# Esquem_tico.net
KiCad netlist of a schematic drawn in Altium Designer
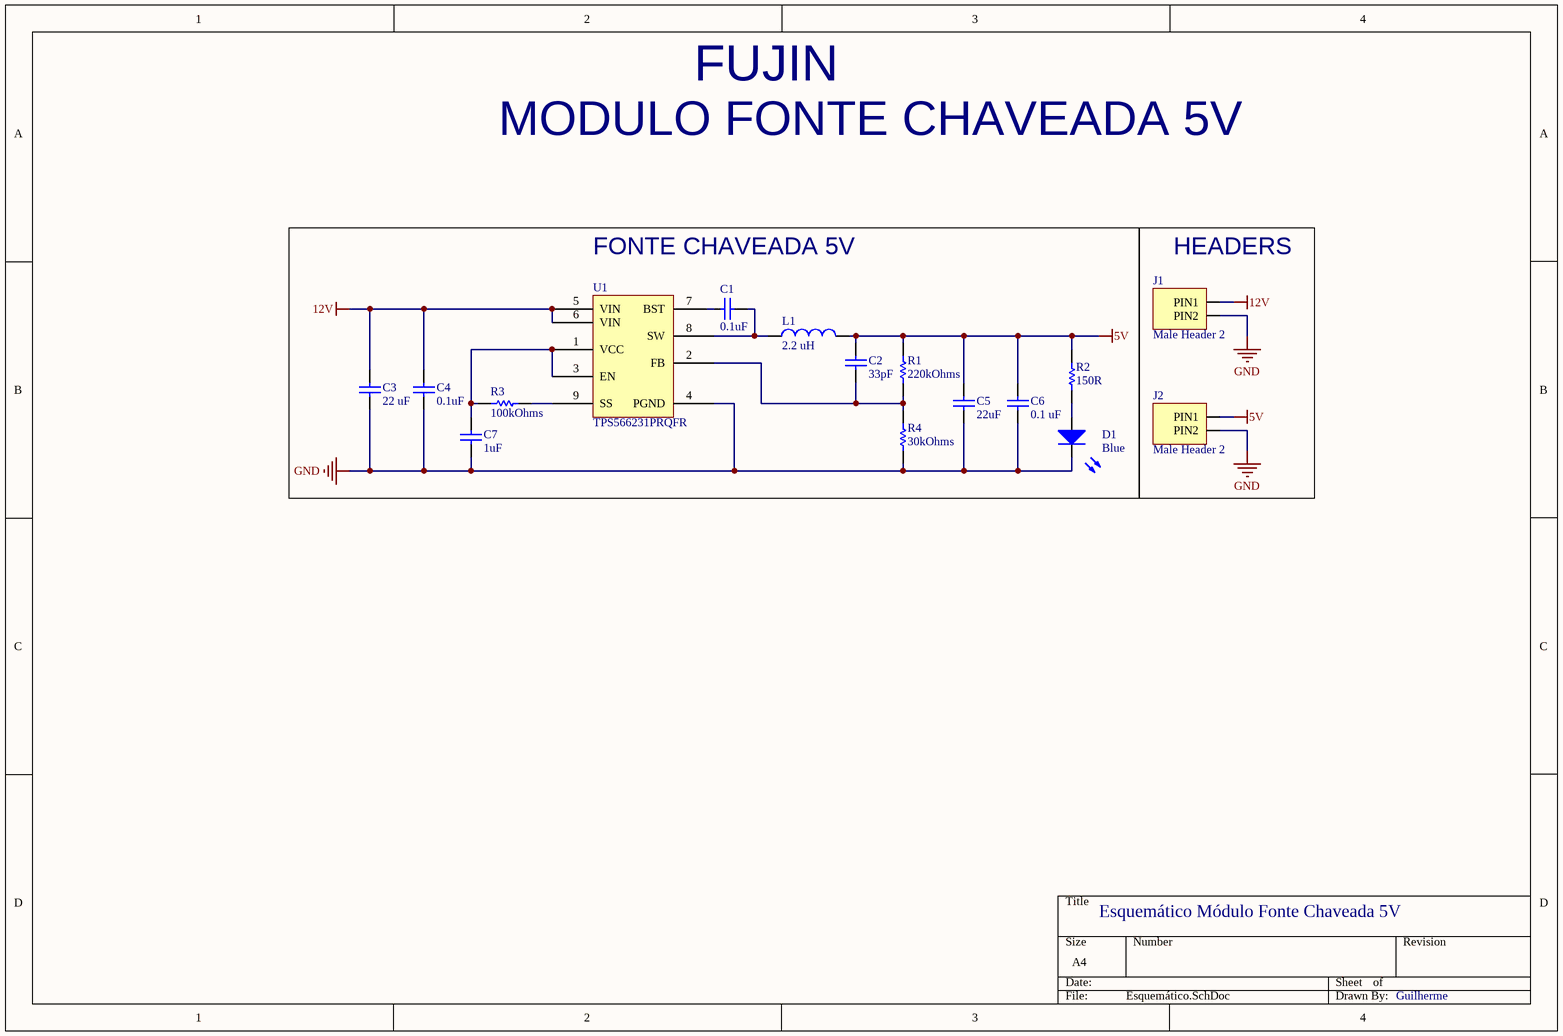
[diagram p0: Esquemático.SchDoc]

(export (version "E")
  (design (tool "Eeschema 10.0.6"))
  (components
    (comp (ref "C1")
      (value "0.1uF")
      (footprint "CAPC1005X55N")
      (description "CAP CER 0.1uF 16V X5R 0402")
      (fields
        (field (name "MANUFACTURER") "Murata")
        (field (name "PART NUMBER") "GRM155R61C104KA88D")
        (field (name "LIBRARY CONTROL - PERSON THAT CHECKED FOOTPRINT") "Guilherme")
        (field (name "LIBRARY CONTROL - PERSON THAT CHECKED SCHEMATIC") "Guilherme")
        (field (name "LIBRARY CONTROL - PERSON THAT DID THE LAST UPDATE FOOTPRINT") "Guilherme")
        (field (name "LIBRARY CONTROL - PERSON THAT DID THE LAST UPDATE SCHEMATIC") "Guilherme")
      )
      (libsource (lib "Uai!Tecas") (part "GRM155R61C104KA88D"))
    )
    (comp (ref "C2")
      (value "33pF")
      (footprint "C0201")
      (description "CAP CER 33pF 25V C0G (NP0) 0201")
      (fields
        (field (name "MANUFACTURER") "TDK")
        (field (name "PART NUMBER") "CGA1A2C0G1E330J030BA")
        (field (name "LIBRARY CONTROL - PERSON THAT CHECKED FOOTPRINT") "Guilherme")
        (field (name "LIBRARY CONTROL - PERSON THAT CHECKED SCHEMATIC") "Guilherme")
        (field (name "LIBRARY CONTROL - PERSON THAT DID THE LAST UPDATE FOOTPRINT") "Stéfany (Ster)")
        (field (name "LIBRARY CONTROL - PERSON THAT DID THE LAST UPDATE SCHEMATIC") "Guilherme")
      )
      (libsource (lib "Uai!Tecas") (part "CGA1A2C0G1E330J030BA"))
    )
    (comp (ref "C3")
      (value "22 uF")
      (footprint "C0805")
      (description "CAP CER 22UF 35V X7R 0805")
      (fields
        (field (name "MANUFACTURER") "TDK")
        (field (name "PART NUMBER") "C2012X5R1V226M125AC")
        (field (name "LIBRARY CONTROL - PERSON THAT DID THE LAST UPDATE FOOTPRINT") "Pierre")
        (field (name "LIBRARY CONTROL - PERSON THAT DID THE LAST UPDATE SCHEMATIC") "Pierre")
      )
      (libsource (lib "Uai!Tecas") (part "C2012X5R1V226M125AC"))
    )
    (comp (ref "C4")
      (value "0.1uF")
      (footprint "CAPC1608X90N")
      (description "CAP CER 0.1uF 100V X7R 0603")
      (fields
        (field (name "MANUFACTURER") "Murata")
        (field (name "PART NUMBER") "GRM188R72A104KA35D")
        (field (name "LIBRARY CONTROL - PERSON THAT CHECKED FOOTPRINT") "Guilherme")
        (field (name "LIBRARY CONTROL - PERSON THAT CHECKED SCHEMATIC") "Guilherme")
        (field (name "LIBRARY CONTROL - PERSON THAT DID THE LAST UPDATE FOOTPRINT") "Guilherme")
        (field (name "LIBRARY CONTROL - PERSON THAT DID THE LAST UPDATE SCHEMATIC") "Guilherme")
      )
      (libsource (lib "Uai!Tecas") (part "GRM188R72A104KA35D"))
    )
    (comp (ref "C5")
      (value "22uF")
      (footprint "C0805")
      (description "CAP CER 22uF 10V X5R 0805")
      (fields
        (field (name "MANUFACTURER") "Taiyo Yuden")
        (field (name "PART NUMBER") "LMK212BJ226MG-T")
        (field (name "LIBRARY CONTROL - PERSON THAT CHECKED FOOTPRINT") "Guilherme")
        (field (name "LIBRARY CONTROL - PERSON THAT CHECKED SCHEMATIC") "Guilherme")
        (field (name "LIBRARY CONTROL - PERSON THAT DID THE LAST UPDATE FOOTPRINT") "Stéfany (Ster)")
        (field (name "LIBRARY CONTROL - PERSON THAT DID THE LAST UPDATE SCHEMATIC") "Guilherme")
      )
      (libsource (lib "Uai!Tecas") (part "LMK212BJ226MG-T"))
    )
    (comp (ref "C6")
      (value "0.1 uF")
      (footprint "C0603")
      (description "CAP CER 0.1uF 25V X7R 0603")
      (fields
        (field (name "MANUFACTURER") "Murata Electronics")
        (field (name "PART NUMBER") "GRM188R71E104KA01D")
        (field (name "LIBRARY CONTROL - PERSON THAT CHECKED FOOTPRINT") "Nikaum")
        (field (name "LIBRARY CONTROL - PERSON THAT CHECKED SCHEMATIC") "Nikaum")
        (field (name "LIBRARY CONTROL - PERSON THAT DID THE LAST UPDATE FOOTPRINT") "Raquel")
        (field (name "LIBRARY CONTROL - PERSON THAT DID THE LAST UPDATE SCHEMATIC") "Nikaum")
      )
      (libsource (lib "Uai!Tecas") (part "GRM188R71E104KA01D"))
    )
    (comp (ref "C7")
      (value "1uF")
      (footprint "C1005")
      (description "CAP CER 1uF 16V X6S 0402")
      (fields
        (field (name "MANUFACTURER") "TDK")
        (field (name "PART NUMBER") "C1005X6S1C105K050BC")
        (field (name "LIBRARY CONTROL - PERSON THAT CHECKED FOOTPRINT") "Guilherme")
        (field (name "LIBRARY CONTROL - PERSON THAT CHECKED SCHEMATIC") "Guilherme")
        (field (name "LIBRARY CONTROL - PERSON THAT DID THE LAST UPDATE FOOTPRINT") "Guilherme")
        (field (name "LIBRARY CONTROL - PERSON THAT DID THE LAST UPDATE SCHEMATIC") "Guilherme")
      )
      (libsource (lib "Uai!Tecas") (part "C1005X6S1C105K050BC"))
    )
    (comp (ref "D1")
      (value "Blue")
      (footprint "DIODO_2-SMD-3215")
      (description "LED 75mW BLUE 45MCD 3215")
      (fields
        (field (name "MANUFACTURER") "Everlight Electronics")
        (field (name "PART NUMBER") "EAST3215BA5")
        (field (name "LIBRARY CONTROL - PERSON THAT CHECKED FOOTPRINT") "Lucas")
        (field (name "LIBRARY CONTROL - PERSON THAT CHECKED SCHEMATIC") "Lucas")
        (field (name "LIBRARY CONTROL - PERSON THAT DID THE LAST UPDATE FOOTPRINT") "Stéfany (Ster)")
        (field (name "LIBRARY CONTROL - PERSON THAT DID THE LAST UPDATE SCHEMATIC") "Stéfany (Ster)")
      )
      (libsource (lib "Uai!Tecas") (part "EAST3215BA5"))
    )
    (comp (ref "J1")
      (value "Male Header 2")
      (footprint "MALE HEADER 2")
      (fields
        (field (name "LIBRARY CONTROL - PERSON THAT DID THE LAST UPDATE SCHEMATIC") "Marcos")
        (field (name "LIBRARY CONTROL - PERSONT THAT DID THE LAST UPDATE FOOTPRINT") "Marcos")
      )
      (libsource (lib "Uai!Tecas") (part "Male Header 2"))
    )
    (comp (ref "J2")
      (value "Male Header 2")
      (footprint "MALE HEADER 2")
      (fields
        (field (name "LIBRARY CONTROL - PERSON THAT DID THE LAST UPDATE SCHEMATIC") "Marcos")
        (field (name "LIBRARY CONTROL - PERSONT THAT DID THE LAST UPDATE FOOTPRINT") "Marcos")
      )
      (libsource (lib "Uai!Tecas") (part "Male Header 2"))
    )
    (comp (ref "L1")
      (value "2.2 uH")
      (footprint "6045")
      (description "IND FIXED 2.2uH 7.5A 0.019OHM")
      (fields
        (field (name "MANUFACTURER") "TDK")
        (field (name "PART NUMBER") "VLS6045EX-2R2N")
        (field (name "LIBRARY CONTROL - PERSON THAT DID THE LAST UPDATE FOOTPRINT") "Marcos")
        (field (name "LIBRARY CONTROL - PERSON THAT DID THE LAST UPDATE SCHEMATIC") "Marcos")
      )
      (libsource (lib "Uai!Tecas") (part "VLS6045EX-2R2N"))
    )
    (comp (ref "R1")
      (value "220kOhms")
      (footprint "RESISTOR_0603")
      (description "RES SMD 220 kOHMS 0,1% 1/10W 0603")
      (fields
        (field (name "MANUFACTURER") "Susumu")
        (field (name "PART NUMBER") "RG1608P-224-B-T5")
        (field (name "LIBRARY CONTROL - PERSON THAT CHECKED FOOTPRINT") "Guilherme")
        (field (name "LIBRARY CONTROL - PERSON THAT CHECKED SCHEMATIC") "Guilherme")
        (field (name "LIBRARY CONTROL - PERSON THAT DID THE LAST UPDATE FOOTPRINT") "Stéfany (Ster)")
        (field (name "LIBRARY CONTROL - PERSON THAT DID THE LAST UPDATE SCHEMATIC") "Guilherme")
      )
      (libsource (lib "Uai!Tecas") (part "RG1608P-224-B-T5"))
    )
    (comp (ref "R2")
      (value "150R")
      (footprint "RESISTOR_0402")
      (description "RES SMD 150 OHM 1% 1/32W 0402")
      (fields
        (field (name "MANUFACTURER") "Vishay")
        (field (name "PART NUMBER") "CRCW0100150RFREL")
        (field (name "LIBRARY CONTROL - PERSON THAT CHECKED FOOTPRINT") "Guilherme")
        (field (name "LIBRARY CONTROL - PERSON THAT CHECKED SCHEMATIC") "Guilherme")
        (field (name "LIBRARY CONTROL - PERSON THAT DID THE LAST UPDATE FOOTPRINT") "Guilherme")
        (field (name "LIBRARY CONTROL - PERSON THAT DID THE LAST UPDATE SCHEMATIC") "Guilherme")
      )
      (libsource (lib "Uai!Tecas") (part "CRCW0100150RFREL"))
    )
    (comp (ref "R3")
      (value "100kOhms")
      (footprint "RESC1005X40N")
      (description "RES SMD 100 kOHMS 1% 1/16W 0402")
      (fields
        (field (name "MANUFACTURER") "Vishay")
        (field (name "PART NUMBER") "CRCW0402100KFKED")
        (field (name "LIBRARY CONTROL - PERSON THAT CHECKED FOOTPRINT") "Guilherme")
        (field (name "LIBRARY CONTROL - PERSON THAT CHECKED SCHEMATIC") "Guilherme")
        (field (name "LIBRARY CONTROL - PERSON THAT DID THE LAST UPDATE FOOTPRINT") "Guilherme")
        (field (name "LIBRARY CONTROL - PERSON THAT DID THE LAST UPDATE SCHEMATIC") "Guilherme")
      )
      (libsource (lib "Uai!Tecas") (part "CRCW0402100KFKED"))
    )
    (comp (ref "R4")
      (value "30kOhms")
      (footprint "RESC1608X55N")
      (description "RES SMD 30 kOHMS 1% 1/10W 0603")
      (fields
        (field (name "MANUFACTURER") "YAGEO")
        (field (name "PART NUMBER") "RC0603FR-0730KL")
        (field (name "LIBRARY CONTROL - PERSON THAT CHECKED FOOTPRINT") "Guilherme")
        (field (name "LIBRARY CONTROL - PERSON THAT CHECKED SCHEMATIC") "Guilherme")
        (field (name "LIBRARY CONTROL - PERSON THAT DID THE LAST UPDATE FOOTPRINT") "Guilherme")
        (field (name "LIBRARY CONTROL - PERSON THAT DID THE LAST UPDATE SCHEMATIC") "Guilherme")
      )
      (libsource (lib "Uai!Tecas") (part "RC0603FR-0730KL"))
    )
    (comp (ref "U1")
      (value "TPS566231PRQFR")
      (footprint "RQF0009A")
      (description "IC REG SWITCHING 4A 0,6V TO 7V")
      (fields
        (field (name "MANUFACTURER") "Texas Instruments")
        (field (name "LIBRARY CONTROL - PERSON THAT CHECKED FOOTPRINT") "Guilherme")
        (field (name "LIBRARY CONTROL - PERSON THAT CHECKED SCHEMATIC") "Guilherme")
        (field (name "LIBRARY CONTROL - PERSON THAT DID THE LAST UPDATE FOOTPRINT") "Marques")
        (field (name "LIBRARY CONTROL - PERSON THAT DID THE LAST UPDATE SCHEMATIC") "Marques")
      )
      (libsource (lib "Uai!Tecas") (part "TPS566231PRQFR"))
    )
  )
  (nets
    (net (code "1") (name "5V") (class "Default")
      (node (ref "C2") (pin "2") (pinfunction "2_2") (pintype "passive"))
      (node (ref "C5") (pin "2") (pinfunction "2_2") (pintype "passive"))
      (node (ref "C6") (pin "2") (pinfunction "2_2") (pintype "passive"))
      (node (ref "J2") (pin "PIN1") (pinfunction "PIN1_PIN1") (pintype "passive"))
      (node (ref "L1") (pin "2") (pinfunction "2_2") (pintype "passive"))
      (node (ref "R1") (pin "2") (pinfunction "2_2") (pintype "passive"))
      (node (ref "R2") (pin "2") (pinfunction "2_2") (pintype "passive"))
    )
    (net (code "2") (name "12V") (class "Default")
      (node (ref "C3") (pin "2") (pinfunction "2_2") (pintype "passive"))
      (node (ref "C4") (pin "2") (pinfunction "2_2") (pintype "passive"))
      (node (ref "J1") (pin "PIN1") (pinfunction "PIN1_PIN1") (pintype "passive"))
      (node (ref "U1") (pin "5") (pinfunction "VIN_5") (pintype "passive"))
      (node (ref "U1") (pin "6") (pinfunction "VIN_6") (pintype "passive"))
    )
    (net (code "3") (name "GND") (class "Default")
      (node (ref "C3") (pin "1") (pinfunction "1_1") (pintype "passive"))
      (node (ref "C4") (pin "1") (pinfunction "1_1") (pintype "passive"))
      (node (ref "C5") (pin "1") (pinfunction "1_1") (pintype "passive"))
      (node (ref "C6") (pin "1") (pinfunction "1_1") (pintype "passive"))
      (node (ref "C7") (pin "1") (pinfunction "1_1") (pintype "passive"))
      (node (ref "D1") (pin "C") (pinfunction "C_C") (pintype "passive"))
      (node (ref "J1") (pin "PIN2") (pinfunction "PIN2_PIN2") (pintype "passive"))
      (node (ref "J2") (pin "PIN2") (pinfunction "PIN2_PIN2") (pintype "passive"))
      (node (ref "R4") (pin "1") (pinfunction "1_1") (pintype "passive"))
      (node (ref "U1") (pin "4") (pinfunction "PGND_4") (pintype "passive"))
    )
    (net (code "4") (name "Net-(D1-PadA)") (class "Default")
      (node (ref "D1") (pin "A") (pinfunction "A_A") (pintype "passive"))
      (node (ref "R2") (pin "1") (pinfunction "1_1") (pintype "passive"))
    )
    (net (code "5") (name "Net-(U1-BST)") (class "Default")
      (node (ref "C1") (pin "2") (pinfunction "2_2") (pintype "passive"))
      (node (ref "U1") (pin "7") (pinfunction "BST_7") (pintype "passive"))
    )
    (net (code "6") (name "Net-(U1-EN)") (class "Default")
      (node (ref "C7") (pin "2") (pinfunction "2_2") (pintype "passive"))
      (node (ref "R3") (pin "1") (pinfunction "1_1") (pintype "passive"))
      (node (ref "U1") (pin "1") (pinfunction "VCC_1") (pintype "passive"))
      (node (ref "U1") (pin "3") (pinfunction "EN_3") (pintype "passive"))
    )
    (net (code "7") (name "Net-(U1-FB)") (class "Default")
      (node (ref "C2") (pin "1") (pinfunction "1_1") (pintype "passive"))
      (node (ref "R1") (pin "1") (pinfunction "1_1") (pintype "passive"))
      (node (ref "R4") (pin "2") (pinfunction "2_2") (pintype "passive"))
      (node (ref "U1") (pin "2") (pinfunction "FB_2") (pintype "passive"))
    )
    (net (code "8") (name "Net-(U1-SS)") (class "Default")
      (node (ref "R3") (pin "2") (pinfunction "2_2") (pintype "passive"))
      (node (ref "U1") (pin "9") (pinfunction "SS_9") (pintype "passive"))
    )
    (net (code "9") (name "Net-(U1-SW)") (class "Default")
      (node (ref "C1") (pin "1") (pinfunction "1_1") (pintype "passive"))
      (node (ref "L1") (pin "1") (pinfunction "1_1") (pintype "passive"))
      (node (ref "U1") (pin "8") (pinfunction "SW_8") (pintype "passive"))
    )
  )
)
